# Driver_Board.net
KiCad netlist of a schematic drawn in Altium Designer
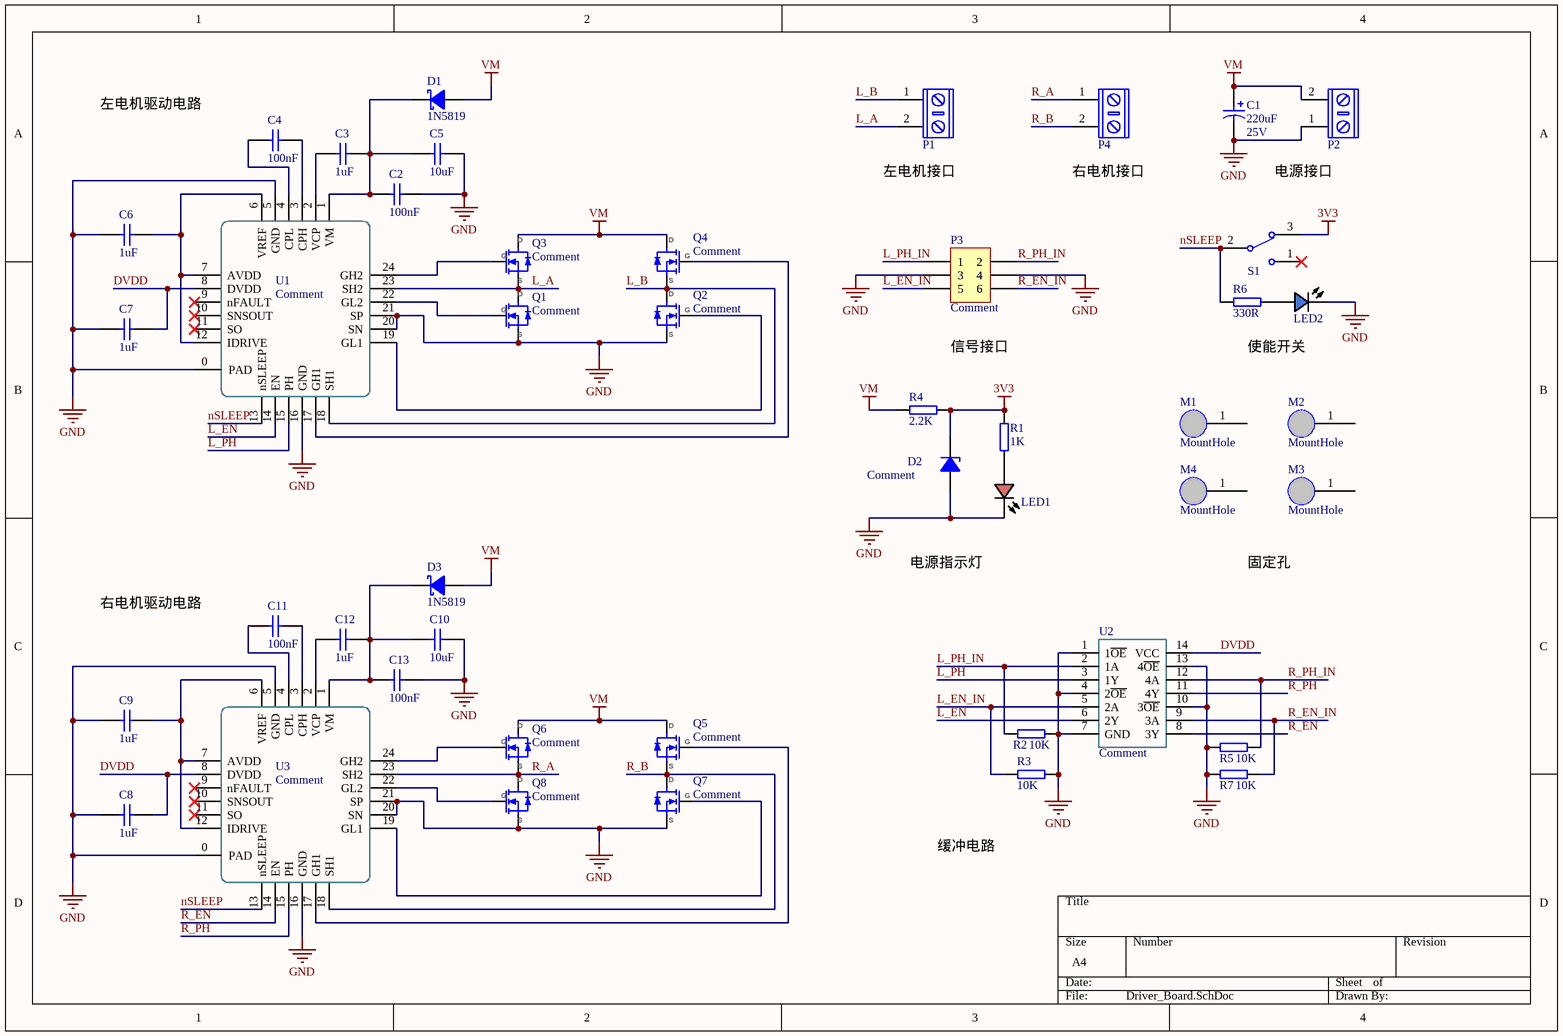
[diagram p0: Driver_Board.SchDoc]

(export (version "E")
  (design (tool "Eeschema 10.0.6"))
  (components
    (comp (ref "C1")
      (value "220uF")
      (footprint "CAPPR3.5-8X11.5")
      (description "Polarized Capacitor (Radial)")
      (fields
        (field (name "VOLTAGE") "25V")
        (field (name "Comment") "Comment")
        (field (name "PUBLISHER") "Altium Limited")
      )
      (libsource (lib "DRV8701E 双驱V1.1 集成封装库") (part "Cap-Elect"))
    )
    (comp (ref "C2")
      (value "100nF")
      (footprint "0805C")
      (description "贴片电容")
      (fields
        (field (name "VOLTAGE") "50V")
        (field (name "TOLERANCE") "±10%")
        (field (name "PUBLISHER") "Altium Limited")
      )
      (libsource (lib "DRV8701E 双驱V1.1 集成封装库") (part "Cap-Chip_1"))
    )
    (comp (ref "C3")
      (value "1uF")
      (footprint "0805")
      (description "贴片电容")
      (fields
        (field (name "VOLTAGE") "25V")
        (field (name "TOLERANCE") "±10%")
        (field (name "PUBLISHER") "Altium Limited")
      )
      (libsource (lib "DRV8701E 双驱V1.1 集成封装库") (part "Cap-Chip_2"))
    )
    (comp (ref "C4")
      (value "100nF")
      (footprint "0805C")
      (description "贴片电容")
      (fields
        (field (name "VOLTAGE") "50V")
        (field (name "TOLERANCE") "±10%")
        (field (name "PUBLISHER") "Altium Limited")
      )
      (libsource (lib "DRV8701E 双驱V1.1 集成封装库") (part "Cap-Chip_1"))
    )
    (comp (ref "C5")
      (value "10uF")
      (footprint "0805")
      (description "贴片电容")
      (fields
        (field (name "VOLTAGE") "25V")
        (field (name "TOLERANCE") "±10%")
        (field (name "PUBLISHER") "Altium Limited")
      )
      (libsource (lib "DRV8701E 双驱V1.1 集成封装库") (part "Cap-Chip"))
    )
    (comp (ref "C6")
      (value "1uF")
      (footprint "0805")
      (description "贴片电容")
      (fields
        (field (name "VOLTAGE") "25V")
        (field (name "TOLERANCE") "±10%")
        (field (name "PUBLISHER") "Altium Limited")
      )
      (libsource (lib "DRV8701E 双驱V1.1 集成封装库") (part "Cap-Chip_2"))
    )
    (comp (ref "C7")
      (value "1uF")
      (footprint "0805")
      (description "贴片电容")
      (fields
        (field (name "VOLTAGE") "25V")
        (field (name "TOLERANCE") "±10%")
        (field (name "PUBLISHER") "Altium Limited")
      )
      (libsource (lib "DRV8701E 双驱V1.1 集成封装库") (part "Cap-Chip_2"))
    )
    (comp (ref "C8")
      (value "1uF")
      (footprint "0805")
      (description "贴片电容")
      (fields
        (field (name "VOLTAGE") "25V")
        (field (name "TOLERANCE") "±10%")
        (field (name "PUBLISHER") "Altium Limited")
      )
      (libsource (lib "DRV8701E 双驱V1.1 集成封装库") (part "Cap-Chip_2"))
    )
    (comp (ref "C9")
      (value "1uF")
      (footprint "0805")
      (description "贴片电容")
      (fields
        (field (name "VOLTAGE") "25V")
        (field (name "TOLERANCE") "±10%")
        (field (name "PUBLISHER") "Altium Limited")
      )
      (libsource (lib "DRV8701E 双驱V1.1 集成封装库") (part "Cap-Chip_2"))
    )
    (comp (ref "C10")
      (value "10uF")
      (footprint "0805")
      (description "贴片电容")
      (fields
        (field (name "VOLTAGE") "25V")
        (field (name "TOLERANCE") "±10%")
        (field (name "PUBLISHER") "Altium Limited")
      )
      (libsource (lib "DRV8701E 双驱V1.1 集成封装库") (part "Cap-Chip"))
    )
    (comp (ref "C11")
      (value "100nF")
      (footprint "0805C")
      (description "贴片电容")
      (fields
        (field (name "VOLTAGE") "50V")
        (field (name "TOLERANCE") "±10%")
        (field (name "PUBLISHER") "Altium Limited")
      )
      (libsource (lib "DRV8701E 双驱V1.1 集成封装库") (part "Cap-Chip_1"))
    )
    (comp (ref "C12")
      (value "1uF")
      (footprint "0805")
      (description "贴片电容")
      (fields
        (field (name "VOLTAGE") "25V")
        (field (name "TOLERANCE") "±10%")
        (field (name "PUBLISHER") "Altium Limited")
      )
      (libsource (lib "DRV8701E 双驱V1.1 集成封装库") (part "Cap-Chip_2"))
    )
    (comp (ref "C13")
      (value "100nF")
      (footprint "0805C")
      (description "贴片电容")
      (fields
        (field (name "VOLTAGE") "50V")
        (field (name "TOLERANCE") "±10%")
        (field (name "PUBLISHER") "Altium Limited")
      )
      (libsource (lib "DRV8701E 双驱V1.1 集成封装库") (part "Cap-Chip_1"))
    )
    (comp (ref "D1")
      (value "Comment")
      (footprint "SOD-123-L")
      (description "肖特基二极管 Diode")
      (fields (field (name "PARTNUMBER") "1N5819") (field (name "PUBLISHER") "Altium Limited"))
      (libsource (lib "DRV8701E 双驱V1.1 集成封装库") (part "Diode Schottky"))
    )
    (comp (ref "D2")
      (value "Comment")
      (footprint "SOD-123-L")
      (description "3.3V稳压二极管 SOD-123")
      (fields (field (name "PUBLISHER") "Altium Limited"))
      (libsource (lib "DRV8701E 双驱V1.1 集成封装库") (part "Diode Zen"))
    )
    (comp (ref "D3")
      (value "Comment")
      (footprint "SOD-123-L")
      (description "肖特基二极管 Diode")
      (fields (field (name "PARTNUMBER") "1N5819") (field (name "PUBLISHER") "Altium Limited"))
      (libsource (lib "DRV8701E 双驱V1.1 集成封装库") (part "Diode Schottky"))
    )
    (comp (ref "LED1")
      (value "Comment")
      (footprint "LEDC1608(0805)")
      (description "Typical Chip LED")
      (fields (field (name "PUBLISHER") "Altium Limited"))
      (libsource (lib "DRV8701E 双驱V1.1 集成封装库") (part "LED Chip Red"))
    )
    (comp (ref "LED2")
      (value "Comment")
      (footprint "LEDC1608(0603)")
      (description "Typical Chip LED")
      (fields (field (name "PUBLISHER") "Altium Limited"))
      (libsource (lib "DRV8701E 双驱V1.1 集成封装库") (part "LED Chip Blue"))
    )
    (comp (ref "M1")
      (value "MountHole")
      (footprint "M3-MountSlot")
      (description "固定孔")
      (libsource (lib "DRV8701E 双驱V1.1 集成封装库") (part "MountHole"))
    )
    (comp (ref "M2")
      (value "MountHole")
      (footprint "M3-MountSlot")
      (description "固定孔")
      (libsource (lib "DRV8701E 双驱V1.1 集成封装库") (part "MountHole"))
    )
    (comp (ref "M3")
      (value "MountHole")
      (footprint "M3-MountSlot")
      (description "固定孔")
      (libsource (lib "DRV8701E 双驱V1.1 集成封装库") (part "MountHole"))
    )
    (comp (ref "M4")
      (value "MountHole")
      (footprint "M3-MountSlot")
      (description "固定孔")
      (libsource (lib "DRV8701E 双驱V1.1 集成封装库") (part "MountHole"))
    )
    (comp (ref "P1")
      (value "KF/WJ/DG 30x connecter")
      (footprint "KF/WJ/DG 301-2p-5.0mm")
      (description "接线端子 2Pin")
      (libsource (lib "DRV8701E 双驱V1.1 集成封装库") (part "KF/WJ/DG 30x"))
    )
    (comp (ref "P2")
      (value "KF/WJ/DG 30x connecter")
      (footprint "KF/WJ/DG 301-2p-5.0mm")
      (description "接线端子 2Pin")
      (libsource (lib "DRV8701E 双驱V1.1 集成封装库") (part "KF/WJ/DG 30x"))
    )
    (comp (ref "P3")
      (value "Comment")
      (footprint "HDR2X3")
      (description "Header, 3-Pin, Dual row")
      (fields (field (name "PUBLISHER") "Altium Limited"))
      (libsource (lib "DRV8701E 双驱V1.1 集成封装库") (part "Header 3X2"))
    )
    (comp (ref "P4")
      (value "KF/WJ/DG 30x connecter")
      (footprint "KF/WJ/DG 301-2p-5.0mm")
      (description "接线端子 2Pin")
      (libsource (lib "DRV8701E 双驱V1.1 集成封装库") (part "KF/WJ/DG 30x"))
    )
    (comp (ref "Q1")
      (value "Comment")
      (footprint "DFN5x6")
      (description "东芝 N沟 MOS")
      (libsource (lib "DRV8701E 双驱V1.1 集成封装库") (part "TPH1R403NL"))
    )
    (comp (ref "Q2")
      (value "Comment")
      (footprint "DFN5x6")
      (description "东芝 N沟 MOS")
      (libsource (lib "DRV8701E 双驱V1.1 集成封装库") (part "TPH1R403NL"))
    )
    (comp (ref "Q3")
      (value "Comment")
      (footprint "DFN5x6")
      (description "东芝 N沟 MOS")
      (libsource (lib "DRV8701E 双驱V1.1 集成封装库") (part "TPH1R403NL"))
    )
    (comp (ref "Q4")
      (value "Comment")
      (footprint "DFN5x6")
      (description "东芝 N沟 MOS")
      (libsource (lib "DRV8701E 双驱V1.1 集成封装库") (part "TPH1R403NL"))
    )
    (comp (ref "Q5")
      (value "Comment")
      (footprint "DFN5x6")
      (description "东芝 N沟 MOS")
      (libsource (lib "DRV8701E 双驱V1.1 集成封装库") (part "TPH1R403NL"))
    )
    (comp (ref "Q6")
      (value "Comment")
      (footprint "DFN5x6")
      (description "东芝 N沟 MOS")
      (libsource (lib "DRV8701E 双驱V1.1 集成封装库") (part "TPH1R403NL"))
    )
    (comp (ref "Q7")
      (value "Comment")
      (footprint "DFN5x6")
      (description "东芝 N沟 MOS")
      (libsource (lib "DRV8701E 双驱V1.1 集成封装库") (part "TPH1R403NL"))
    )
    (comp (ref "Q8")
      (value "Comment")
      (footprint "DFN5x6")
      (description "东芝 N沟 MOS")
      (libsource (lib "DRV8701E 双驱V1.1 集成封装库") (part "TPH1R403NL"))
    )
    (comp (ref "R1")
      (value "1K")
      (footprint "RESC1608[0603]S-N")
      (description "贴片电阻")
      (fields
        (field (name "TOLERANCE") "±1%")
        (field (name "Comment") "Comment")
        (field (name "PUBLISHER") "Altium Limited")
      )
      (libsource (lib "DRV8701E 双驱V1.1 集成封装库") (part "Res-Chip_2"))
    )
    (comp (ref "R2")
      (value "10K")
      (footprint "RESC1608[0603]S-N")
      (description "贴片电阻")
      (fields
        (field (name "TOLERANCE") "±1%")
        (field (name "Comment") "Comment")
        (field (name "PUBLISHER") "Altium Limited")
      )
      (libsource (lib "DRV8701E 双驱V1.1 集成封装库") (part "Res-Chip_1"))
    )
    (comp (ref "R3")
      (value "10K")
      (footprint "RESC1608[0603]S-N")
      (description "贴片电阻")
      (fields
        (field (name "TOLERANCE") "±1%")
        (field (name "Comment") "Comment")
        (field (name "PUBLISHER") "Altium Limited")
      )
      (libsource (lib "DRV8701E 双驱V1.1 集成封装库") (part "Res-Chip_1"))
    )
    (comp (ref "R4")
      (value "2.2K")
      (footprint "RESC1608[0603]S-N")
      (description "贴片电阻")
      (fields
        (field (name "TOLERANCE") "±1%")
        (field (name "Comment") "Comment")
        (field (name "PUBLISHER") "Altium Limited")
      )
      (libsource (lib "DRV8701E 双驱V1.1 集成封装库") (part "Res-Chip"))
    )
    (comp (ref "R5")
      (value "10K")
      (footprint "RESC1608[0603]S-N")
      (description "贴片电阻")
      (fields
        (field (name "TOLERANCE") "±1%")
        (field (name "Comment") "Comment")
        (field (name "PUBLISHER") "Altium Limited")
      )
      (libsource (lib "DRV8701E 双驱V1.1 集成封装库") (part "Res-Chip_1"))
    )
    (comp (ref "R6")
      (value "330R")
      (footprint "RESC1608[0603]S-N")
      (description "贴片电阻")
      (fields
        (field (name "TOLERANCE") "±1%")
        (field (name "Comment") "Comment")
        (field (name "PUBLISHER") "Altium Limited")
      )
      (libsource (lib "DRV8701E 双驱V1.1 集成封装库") (part "Res-Chip_3"))
    )
    (comp (ref "R7")
      (value "10K")
      (footprint "RESC1608[0603]S-N")
      (description "贴片电阻")
      (fields
        (field (name "TOLERANCE") "±1%")
        (field (name "Comment") "Comment")
        (field (name "PUBLISHER") "Altium Limited")
      )
      (libsource (lib "DRV8701E 双驱V1.1 集成封装库") (part "Res-Chip_1"))
    )
    (comp (ref "S1")
      (value "Comment")
      (footprint "SS12D10")
      (description "单刀双掷开关 3脚船型、钮子、拨动开关 SPDT Subminiature Toggle Switch")
      (fields (field (name "PUBLISHER") "Altium Limited"))
      (libsource (lib "DRV8701E 双驱V1.1 集成封装库") (part "SW-SPDT"))
    )
    (comp (ref "U1")
      (value "Comment")
      (footprint "QFN24-4x4")
      (description "DRV8701E Ti全桥驱动芯片")
      (libsource (lib "DRV8701E 双驱V1.1 集成封装库") (part "DRV8701E"))
    )
    (comp (ref "U2")
      (value "Comment")
      (footprint "SOP14-1")
      (description "三态输出的四路缓冲器 TSSOP-20")
      (libsource (lib "DRV8701E 双驱V1.1 集成封装库") (part "SN74HC125PWR"))
    )
    (comp (ref "U3")
      (value "Comment")
      (footprint "SOP14-1")
      (description "DRV8701E Ti全桥驱动芯片")
      (libsource (lib "DRV8701E 双驱V1.1 集成封装库") (part "DRV8701E"))
    )
  )
  (nets
    (net (code "1") (name "/DVDD") (class "Default")
      (node (ref "C7") (pin "2") (pinfunction "2_2") (pintype "passive"))
      (node (ref "C8") (pin "2") (pinfunction "2_2") (pintype "passive"))
      (node (ref "U1") (pin "8") (pinfunction "DVDD_8") (pintype "passive"))
      (node (ref "U2") (pin "14") (pinfunction "VCC_14") (pintype "passive"))
      (node (ref "U3") (pin "8") (pinfunction "DVDD_8") (pintype "passive"))
    )
    (net (code "2") (name "/L_A") (class "Default")
      (node (ref "P1") (pin "2") (pinfunction "2_2") (pintype "passive"))
      (node (ref "Q1") (pin "1") (pinfunction "D_1") (pintype "passive"))
      (node (ref "Q3") (pin "3") (pinfunction "S_3") (pintype "passive"))
      (node (ref "U1") (pin "23") (pinfunction "SH2_23") (pintype "passive"))
    )
    (net (code "3") (name "/L_B") (class "Default")
      (node (ref "P1") (pin "1") (pinfunction "1_1") (pintype "passive"))
      (node (ref "Q2") (pin "1") (pinfunction "D_1") (pintype "passive"))
      (node (ref "Q4") (pin "3") (pinfunction "S_3") (pintype "passive"))
      (node (ref "U1") (pin "18") (pinfunction "SH1_18") (pintype "passive"))
    )
    (net (code "4") (name "/L_EN") (class "Default")
      (node (ref "U1") (pin "14") (pinfunction "EN_14") (pintype "passive"))
      (node (ref "U2") (pin "6") (pinfunction "2Y_6") (pintype "passive"))
    )
    (net (code "5") (name "/L_EN_IN") (class "Default")
      (node (ref "P3") (pin "5") (pinfunction "5_5") (pintype "passive"))
      (node (ref "R3") (pin "1") (pinfunction "1_1") (pintype "passive"))
      (node (ref "U2") (pin "5") (pinfunction "2A_5") (pintype "passive"))
    )
    (net (code "6") (name "/L_PH") (class "Default")
      (node (ref "U1") (pin "15") (pinfunction "PH_15") (pintype "passive"))
      (node (ref "U2") (pin "3") (pinfunction "1Y_3") (pintype "passive"))
    )
    (net (code "7") (name "/L_PH_IN") (class "Default")
      (node (ref "P3") (pin "1") (pinfunction "1_1") (pintype "passive"))
      (node (ref "R2") (pin "1") (pinfunction "1_1") (pintype "passive"))
      (node (ref "U2") (pin "2") (pinfunction "1A_2") (pintype "passive"))
    )
    (net (code "8") (name "/R_A") (class "Default")
      (node (ref "P4") (pin "1") (pinfunction "1_1") (pintype "passive"))
      (node (ref "Q6") (pin "3") (pinfunction "S_3") (pintype "passive"))
      (node (ref "Q8") (pin "1") (pinfunction "D_1") (pintype "passive"))
      (node (ref "U3") (pin "23") (pinfunction "SH2_23") (pintype "passive"))
    )
    (net (code "9") (name "/R_B") (class "Default")
      (node (ref "P4") (pin "2") (pinfunction "2_2") (pintype "passive"))
      (node (ref "Q5") (pin "3") (pinfunction "S_3") (pintype "passive"))
      (node (ref "Q7") (pin "1") (pinfunction "D_1") (pintype "passive"))
      (node (ref "U3") (pin "18") (pinfunction "SH1_18") (pintype "passive"))
    )
    (net (code "10") (name "/R_EN") (class "Default")
      (node (ref "U2") (pin "8") (pinfunction "3Y_8") (pintype "passive"))
      (node (ref "U3") (pin "14") (pinfunction "EN_14") (pintype "passive"))
    )
    (net (code "11") (name "/R_EN_IN") (class "Default")
      (node (ref "P3") (pin "6") (pinfunction "6_6") (pintype "passive"))
      (node (ref "R7") (pin "2") (pinfunction "2_2") (pintype "passive"))
      (node (ref "U2") (pin "9") (pinfunction "3A_9") (pintype "passive"))
    )
    (net (code "12") (name "/R_PH") (class "Default")
      (node (ref "U2") (pin "11") (pinfunction "4Y_11") (pintype "passive"))
      (node (ref "U3") (pin "15") (pinfunction "PH_15") (pintype "passive"))
    )
    (net (code "13") (name "/R_PH_IN") (class "Default")
      (node (ref "P3") (pin "2") (pinfunction "2_2") (pintype "passive"))
      (node (ref "R5") (pin "2") (pinfunction "2_2") (pintype "passive"))
      (node (ref "U2") (pin "12") (pinfunction "4A_12") (pintype "passive"))
    )
    (net (code "14") (name "/nSLEEP") (class "Default")
      (node (ref "R6") (pin "1") (pinfunction "1_1") (pintype "passive"))
      (node (ref "S1") (pin "2") (pintype "passive"))
      (node (ref "U1") (pin "13") (pinfunction "nSLEEP_13") (pintype "passive"))
      (node (ref "U3") (pin "13") (pinfunction "nSLEEP_13") (pintype "passive"))
    )
    (net (code "15") (name "3V3") (class "Default")
      (node (ref "D2") (pin "K") (pinfunction "K_K") (pintype "passive"))
      (node (ref "R1") (pin "2") (pinfunction "2_2") (pintype "passive"))
      (node (ref "R4") (pin "2") (pinfunction "2_2") (pintype "passive"))
      (node (ref "S1") (pin "3") (pintype "passive"))
    )
    (net (code "16") (name "GND") (class "Default")
      (node (ref "C1") (pin "2") (pinfunction "2_2") (pintype "passive"))
      (node (ref "C10") (pin "2") (pinfunction "2_2") (pintype "passive"))
      (node (ref "C13") (pin "2") (pinfunction "2_2") (pintype "passive"))
      (node (ref "C2") (pin "2") (pinfunction "2_2") (pintype "passive"))
      (node (ref "C5") (pin "2") (pinfunction "2_2") (pintype "passive"))
      (node (ref "C6") (pin "1") (pinfunction "1_1") (pintype "passive"))
      (node (ref "C7") (pin "1") (pinfunction "1_1") (pintype "passive"))
      (node (ref "C8") (pin "1") (pinfunction "1_1") (pintype "passive"))
      (node (ref "C9") (pin "1") (pinfunction "1_1") (pintype "passive"))
      (node (ref "D2") (pin "A") (pinfunction "A_A") (pintype "passive"))
      (node (ref "LED1") (pin "C") (pinfunction "C_C") (pintype "passive"))
      (node (ref "LED2") (pin "C") (pinfunction "C_C") (pintype "passive"))
      (node (ref "P2") (pin "1") (pinfunction "1_1") (pintype "passive"))
      (node (ref "P3") (pin "3") (pinfunction "3_3") (pintype "passive"))
      (node (ref "P3") (pin "4") (pinfunction "4_4") (pintype "passive"))
      (node (ref "Q1") (pin "3") (pinfunction "S_3") (pintype "passive"))
      (node (ref "Q2") (pin "3") (pinfunction "S_3") (pintype "passive"))
      (node (ref "Q7") (pin "3") (pinfunction "S_3") (pintype "passive"))
      (node (ref "Q8") (pin "3") (pinfunction "S_3") (pintype "passive"))
      (node (ref "R2") (pin "2") (pinfunction "2_2") (pintype "passive"))
      (node (ref "R3") (pin "2") (pinfunction "2_2") (pintype "passive"))
      (node (ref "R5") (pin "1") (pinfunction "1_1") (pintype "passive"))
      (node (ref "R7") (pin "1") (pinfunction "1_1") (pintype "passive"))
      (node (ref "U1") (pin "0") (pinfunction "PAD_0") (pintype "passive"))
      (node (ref "U1") (pin "16") (pinfunction "GND_16") (pintype "passive"))
      (node (ref "U1") (pin "20") (pinfunction "SN_20") (pintype "passive"))
      (node (ref "U1") (pin "21") (pinfunction "SP_21") (pintype "passive"))
      (node (ref "U1") (pin "5") (pinfunction "GND_5") (pintype "passive"))
      (node (ref "U2") (pin "1") (pinfunction "1~{OE}_1") (pintype "passive"))
      (node (ref "U2") (pin "10") (pinfunction "3~{OE}_10") (pintype "passive"))
      (node (ref "U2") (pin "13") (pinfunction "4~{OE}_13") (pintype "passive"))
      (node (ref "U2") (pin "4") (pinfunction "2~{OE}_4") (pintype "passive"))
      (node (ref "U2") (pin "7") (pinfunction "GND_7") (pintype "passive"))
      (node (ref "U3") (pin "0") (pinfunction "PAD_0") (pintype "passive"))
      (node (ref "U3") (pin "16") (pinfunction "GND_16") (pintype "passive"))
      (node (ref "U3") (pin "20") (pinfunction "SN_20") (pintype "passive"))
      (node (ref "U3") (pin "21") (pinfunction "SP_21") (pintype "passive"))
      (node (ref "U3") (pin "5") (pinfunction "GND_5") (pintype "passive"))
    )
    (net (code "17") (name "Net-(LED1-PadA)") (class "Default")
      (node (ref "LED1") (pin "A") (pinfunction "A_A") (pintype "passive"))
      (node (ref "R1") (pin "1") (pinfunction "1_1") (pintype "passive"))
    )
    (net (code "18") (name "Net-(LED2-PadA)") (class "Default")
      (node (ref "LED2") (pin "A") (pinfunction "A_A") (pintype "passive"))
      (node (ref "R6") (pin "2") (pinfunction "2_2") (pintype "passive"))
    )
    (net (code "19") (name "Net-(Q1-G)") (class "Default")
      (node (ref "Q1") (pin "2") (pinfunction "G_2") (pintype "passive"))
      (node (ref "U1") (pin "22") (pinfunction "GL2_22") (pintype "passive"))
    )
    (net (code "20") (name "Net-(Q2-G)") (class "Default")
      (node (ref "Q2") (pin "2") (pinfunction "G_2") (pintype "passive"))
      (node (ref "U1") (pin "19") (pinfunction "GL1_19") (pintype "passive"))
    )
    (net (code "21") (name "Net-(Q3-G)") (class "Default")
      (node (ref "Q3") (pin "2") (pinfunction "G_2") (pintype "passive"))
      (node (ref "U1") (pin "24") (pinfunction "GH2_24") (pintype "passive"))
    )
    (net (code "22") (name "Net-(Q4-G)") (class "Default")
      (node (ref "Q4") (pin "2") (pinfunction "G_2") (pintype "passive"))
      (node (ref "U1") (pin "17") (pinfunction "GH1_17") (pintype "passive"))
    )
    (net (code "23") (name "Net-(Q5-G)") (class "Default")
      (node (ref "Q5") (pin "2") (pinfunction "G_2") (pintype "passive"))
      (node (ref "U3") (pin "17") (pinfunction "GH1_17") (pintype "passive"))
    )
    (net (code "24") (name "Net-(Q6-G)") (class "Default")
      (node (ref "Q6") (pin "2") (pinfunction "G_2") (pintype "passive"))
      (node (ref "U3") (pin "24") (pinfunction "GH2_24") (pintype "passive"))
    )
    (net (code "25") (name "Net-(Q7-G)") (class "Default")
      (node (ref "Q7") (pin "2") (pinfunction "G_2") (pintype "passive"))
      (node (ref "U3") (pin "19") (pinfunction "GL1_19") (pintype "passive"))
    )
    (net (code "26") (name "Net-(Q8-G)") (class "Default")
      (node (ref "Q8") (pin "2") (pinfunction "G_2") (pintype "passive"))
      (node (ref "U3") (pin "22") (pinfunction "GL2_22") (pintype "passive"))
    )
    (net (code "27") (name "Net-(U1-AVDD)") (class "Default")
      (node (ref "C6") (pin "2") (pinfunction "2_2") (pintype "passive"))
      (node (ref "U1") (pin "12") (pinfunction "IDRIVE_12") (pintype "passive"))
      (node (ref "U1") (pin "6") (pinfunction "VREF_6") (pintype "passive"))
      (node (ref "U1") (pin "7") (pinfunction "AVDD_7") (pintype "passive"))
    )
    (net (code "28") (name "Net-(U1-CPH)") (class "Default")
      (node (ref "C4") (pin "2") (pinfunction "2_2") (pintype "passive"))
      (node (ref "U1") (pin "3") (pinfunction "CPH_3") (pintype "passive"))
    )
    (net (code "29") (name "Net-(U1-CPL)") (class "Default")
      (node (ref "C4") (pin "1") (pinfunction "1_1") (pintype "passive"))
      (node (ref "U1") (pin "4") (pinfunction "CPL_4") (pintype "passive"))
    )
    (net (code "30") (name "Net-(U1-VCP)") (class "Default")
      (node (ref "C3") (pin "1") (pinfunction "1_1") (pintype "passive"))
      (node (ref "U1") (pin "2") (pinfunction "VCP_2") (pintype "passive"))
    )
    (net (code "31") (name "Net-(U1-VM)") (class "Default")
      (node (ref "C2") (pin "1") (pinfunction "1_1") (pintype "passive"))
      (node (ref "C3") (pin "2") (pinfunction "2_2") (pintype "passive"))
      (node (ref "C5") (pin "1") (pinfunction "1_1") (pintype "passive"))
      (node (ref "D1") (pin "K") (pinfunction "K_K") (pintype "passive"))
      (node (ref "U1") (pin "1") (pinfunction "VM_1") (pintype "passive"))
    )
    (net (code "32") (name "Net-(U3-AVDD)") (class "Default")
      (node (ref "C9") (pin "2") (pinfunction "2_2") (pintype "passive"))
      (node (ref "U3") (pin "12") (pinfunction "IDRIVE_12") (pintype "passive"))
      (node (ref "U3") (pin "6") (pinfunction "VREF_6") (pintype "passive"))
      (node (ref "U3") (pin "7") (pinfunction "AVDD_7") (pintype "passive"))
    )
    (net (code "33") (name "Net-(U3-CPH)") (class "Default")
      (node (ref "C11") (pin "2") (pinfunction "2_2") (pintype "passive"))
      (node (ref "U3") (pin "3") (pinfunction "CPH_3") (pintype "passive"))
    )
    (net (code "34") (name "Net-(U3-CPL)") (class "Default")
      (node (ref "C11") (pin "1") (pinfunction "1_1") (pintype "passive"))
      (node (ref "U3") (pin "4") (pinfunction "CPL_4") (pintype "passive"))
    )
    (net (code "35") (name "Net-(U3-VCP)") (class "Default")
      (node (ref "C12") (pin "1") (pinfunction "1_1") (pintype "passive"))
      (node (ref "U3") (pin "2") (pinfunction "VCP_2") (pintype "passive"))
    )
    (net (code "36") (name "Net-(U3-VM)") (class "Default")
      (node (ref "C10") (pin "1") (pinfunction "1_1") (pintype "passive"))
      (node (ref "C12") (pin "2") (pinfunction "2_2") (pintype "passive"))
      (node (ref "C13") (pin "1") (pinfunction "1_1") (pintype "passive"))
      (node (ref "D3") (pin "K") (pinfunction "K_K") (pintype "passive"))
      (node (ref "U3") (pin "1") (pinfunction "VM_1") (pintype "passive"))
    )
    (net (code "37") (name "VM") (class "Default")
      (node (ref "C1") (pin "1") (pinfunction "1_1") (pintype "passive"))
      (node (ref "D1") (pin "A") (pinfunction "A_A") (pintype "passive"))
      (node (ref "D3") (pin "A") (pinfunction "A_A") (pintype "passive"))
      (node (ref "P2") (pin "2") (pinfunction "2_2") (pintype "passive"))
      (node (ref "Q3") (pin "1") (pinfunction "D_1") (pintype "passive"))
      (node (ref "Q4") (pin "1") (pinfunction "D_1") (pintype "passive"))
      (node (ref "Q5") (pin "1") (pinfunction "D_1") (pintype "passive"))
      (node (ref "Q6") (pin "1") (pinfunction "D_1") (pintype "passive"))
      (node (ref "R4") (pin "1") (pinfunction "1_1") (pintype "passive"))
    )
    (net (code "38") (name "unconnected-(M1-Pad1)") (class "Default")
      (node (ref "M1") (pin "1") (pinfunction "1_1") (pintype "passive"))
    )
    (net (code "39") (name "unconnected-(M2-Pad1)") (class "Default")
      (node (ref "M2") (pin "1") (pinfunction "1_1") (pintype "passive"))
    )
    (net (code "40") (name "unconnected-(M3-Pad1)") (class "Default")
      (node (ref "M3") (pin "1") (pinfunction "1_1") (pintype "passive"))
    )
    (net (code "41") (name "unconnected-(M4-Pad1)") (class "Default")
      (node (ref "M4") (pin "1") (pinfunction "1_1") (pintype "passive"))
    )
    (net (code "42") (name "unconnected-(S1-Pad1)") (class "Default")
      (node (ref "S1") (pin "1") (pintype "passive+no_connect"))
    )
    (net (code "43") (name "unconnected-(U1-SNSOUT-Pad10)") (class "Default")
      (node (ref "U1") (pin "10") (pinfunction "SNSOUT_10") (pintype "passive+no_connect"))
    )
    (net (code "44") (name "unconnected-(U1-SO-Pad11)") (class "Default")
      (node (ref "U1") (pin "11") (pinfunction "SO_11") (pintype "passive+no_connect"))
    )
    (net (code "45") (name "unconnected-(U1-nFAULT-Pad9)") (class "Default")
      (node (ref "U1") (pin "9") (pinfunction "nFAULT_9") (pintype "passive+no_connect"))
    )
    (net (code "46") (name "unconnected-(U3-SNSOUT-Pad10)") (class "Default")
      (node (ref "U3") (pin "10") (pinfunction "SNSOUT_10") (pintype "passive+no_connect"))
    )
    (net (code "47") (name "unconnected-(U3-SO-Pad11)") (class "Default")
      (node (ref "U3") (pin "11") (pinfunction "SO_11") (pintype "passive+no_connect"))
    )
    (net (code "48") (name "unconnected-(U3-nFAULT-Pad9)") (class "Default")
      (node (ref "U3") (pin "9") (pinfunction "nFAULT_9") (pintype "passive+no_connect"))
    )
  )
)
